# 3rd_ESC.net
KiCad netlist of a schematic drawn in EAGLE
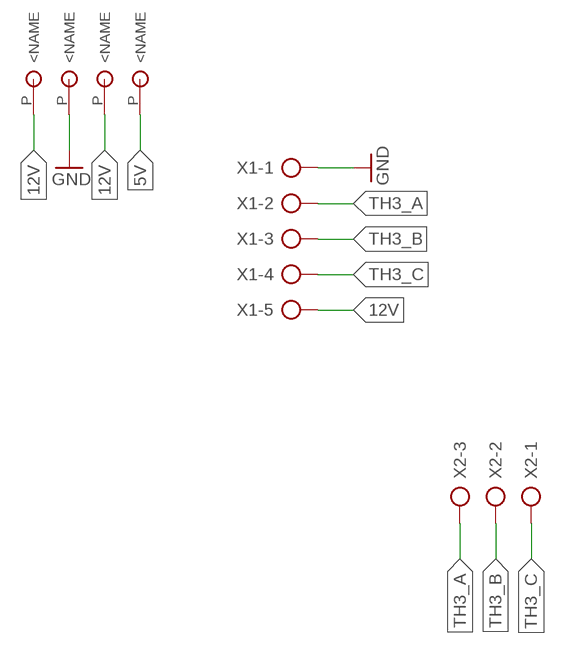
[diagram p0: schematic, sheet 1]

(export (version "E")
  (design (tool "Eeschema 10.0.6"))
  (components
    (comp (ref "U$1")
      (value "CU-SPACER")
      (footprint "eagle-import:CU-SPACER")
      (libsource (lib "eagle-import") (part "CU-SPACER"))
    )
    (comp (ref "U$2")
      (value "CU-SPACER")
      (footprint "eagle-import:CU-SPACER")
      (libsource (lib "eagle-import") (part "CU-SPACER"))
    )
    (comp (ref "U$3")
      (value "CU-SPACER")
      (footprint "eagle-import:CU-SPACER")
      (libsource (lib "eagle-import") (part "CU-SPACER"))
    )
    (comp (ref "U$4")
      (value "CU-SPACER")
      (footprint "eagle-import:CU-SPACER")
      (libsource (lib "eagle-import") (part "CU-SPACER"))
    )
    (comp (ref "X1")
      (value "AK500/5")
      (footprint "eagle-import:AK500_5")
      (libsource (lib "eagle-import") (part "AK500/5"))
    )
    (comp (ref "X2")
      (value "AK500/3")
      (footprint "eagle-import:AK500_3")
      (libsource (lib "eagle-import") (part "AK500/3"))
    )
  )
  (nets
    (net (code "1") (name "5V") (class "Default")
      (node (ref "U$4") (pin "P") (pinfunction "<NAME_P") (pintype "bidirectional"))
    )
    (net (code "2") (name "12V") (class "Default")
      (node (ref "U$1") (pin "P") (pinfunction "<NAME_P") (pintype "bidirectional"))
      (node (ref "U$3") (pin "P") (pinfunction "<NAME_P") (pintype "bidirectional"))
      (node (ref "X1") (pin "5") (pinfunction "KL_5") (pintype "passive"))
    )
    (net (code "3") (name "GND") (class "Default")
      (node (ref "U$2") (pin "P") (pinfunction "<NAME_P") (pintype "bidirectional"))
      (node (ref "X1") (pin "1") (pinfunction "KL_1") (pintype "passive"))
    )
    (net (code "4") (name "TH3_A") (class "Default")
      (node (ref "X1") (pin "2") (pinfunction "KL_2") (pintype "passive"))
      (node (ref "X2") (pin "3") (pinfunction "KL_3") (pintype "passive"))
    )
    (net (code "5") (name "TH3_B") (class "Default")
      (node (ref "X1") (pin "3") (pinfunction "KL_3") (pintype "passive"))
      (node (ref "X2") (pin "2") (pinfunction "KL_2") (pintype "passive"))
    )
    (net (code "6") (name "TH3_C") (class "Default")
      (node (ref "X1") (pin "4") (pinfunction "KL_4") (pintype "passive"))
      (node (ref "X2") (pin "1") (pinfunction "KL_1") (pintype "passive"))
    )
  )
)
